# 00_Principal.net
KiCad netlist of a schematic drawn in Altium Designer
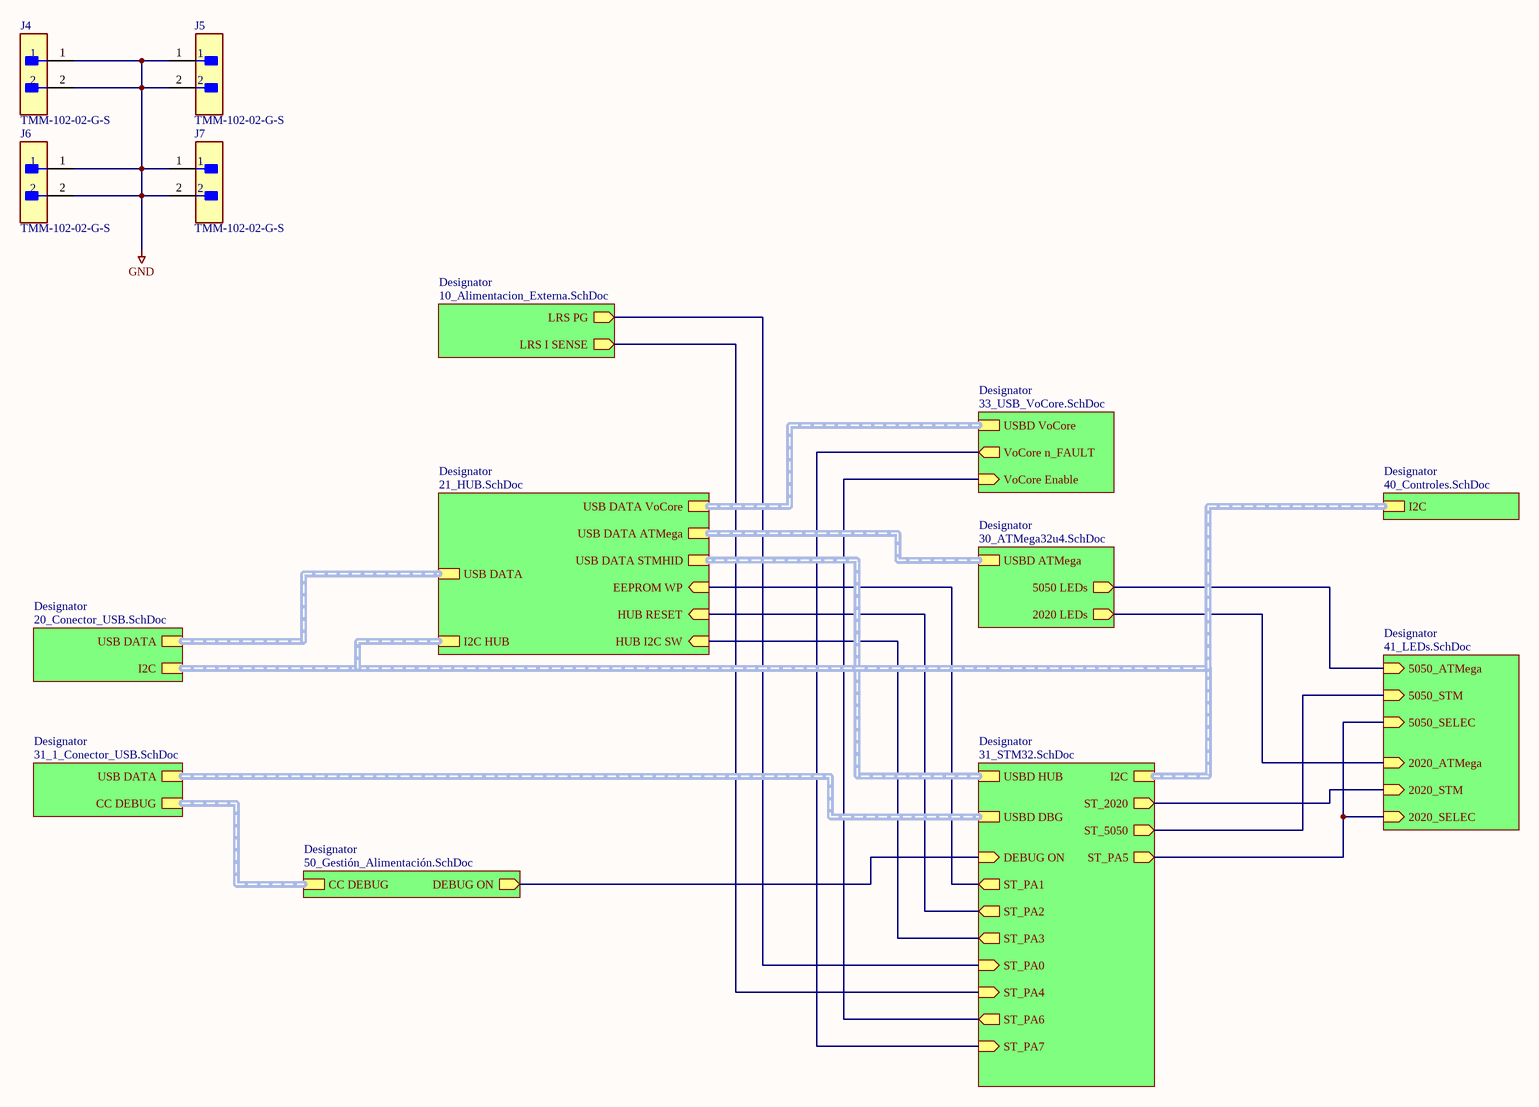
[diagram p0: 00_Principal.SchDoc]

(export (version "E")
  (design (tool "Eeschema 10.0.6"))
  (components
    (comp (ref "J4")
      (value "TMM-102-02-G-S")
      (footprint "FP-TMM-102-02-G-S-MFG")
      (description "CONN HEADER VERT 2POS 2MM")
      (libsource (lib "Altium Content Vault") (part "3bc925449376181038e59eaffc5286c"))
    )
    (comp (ref "J5")
      (value "TMM-102-02-G-S")
      (footprint "FP-TMM-102-02-G-S-MFG")
      (description "CONN HEADER VERT 2POS 2MM")
      (libsource (lib "") (part "3bc925449376181038e59eaffc5286c_1"))
    )
    (comp (ref "J6")
      (value "TMM-102-02-G-S")
      (footprint "FP-TMM-102-02-G-S-MFG")
      (description "CONN HEADER VERT 2POS 2MM")
      (libsource (lib "Altium Content Vault") (part "3bc925449376181038e59eaffc5286c"))
    )
    (comp (ref "J7")
      (value "TMM-102-02-G-S")
      (footprint "FP-TMM-102-02-G-S-MFG")
      (description "CONN HEADER VERT 2POS 2MM")
      (libsource (lib "") (part "3bc925449376181038e59eaffc5286c_1"))
    )
  )
  (nets
    (net (code "21") (name "GND") (class "Default")
      (node (ref "J4") (pin "1") (pinfunction "1_1") (pintype "passive"))
      (node (ref "J4") (pin "2") (pinfunction "2_2") (pintype "passive"))
      (node (ref "J5") (pin "1") (pinfunction "1_1") (pintype "passive"))
      (node (ref "J5") (pin "2") (pinfunction "2_2") (pintype "passive"))
      (node (ref "J6") (pin "1") (pinfunction "1_1") (pintype "passive"))
      (node (ref "J6") (pin "2") (pinfunction "2_2") (pintype "passive"))
      (node (ref "J7") (pin "1") (pinfunction "1_1") (pintype "passive"))
      (node (ref "J7") (pin "2") (pinfunction "2_2") (pintype "passive"))
    )
  )
)
